# RP2040.net
KiCad netlist of a schematic drawn in Altium Designer
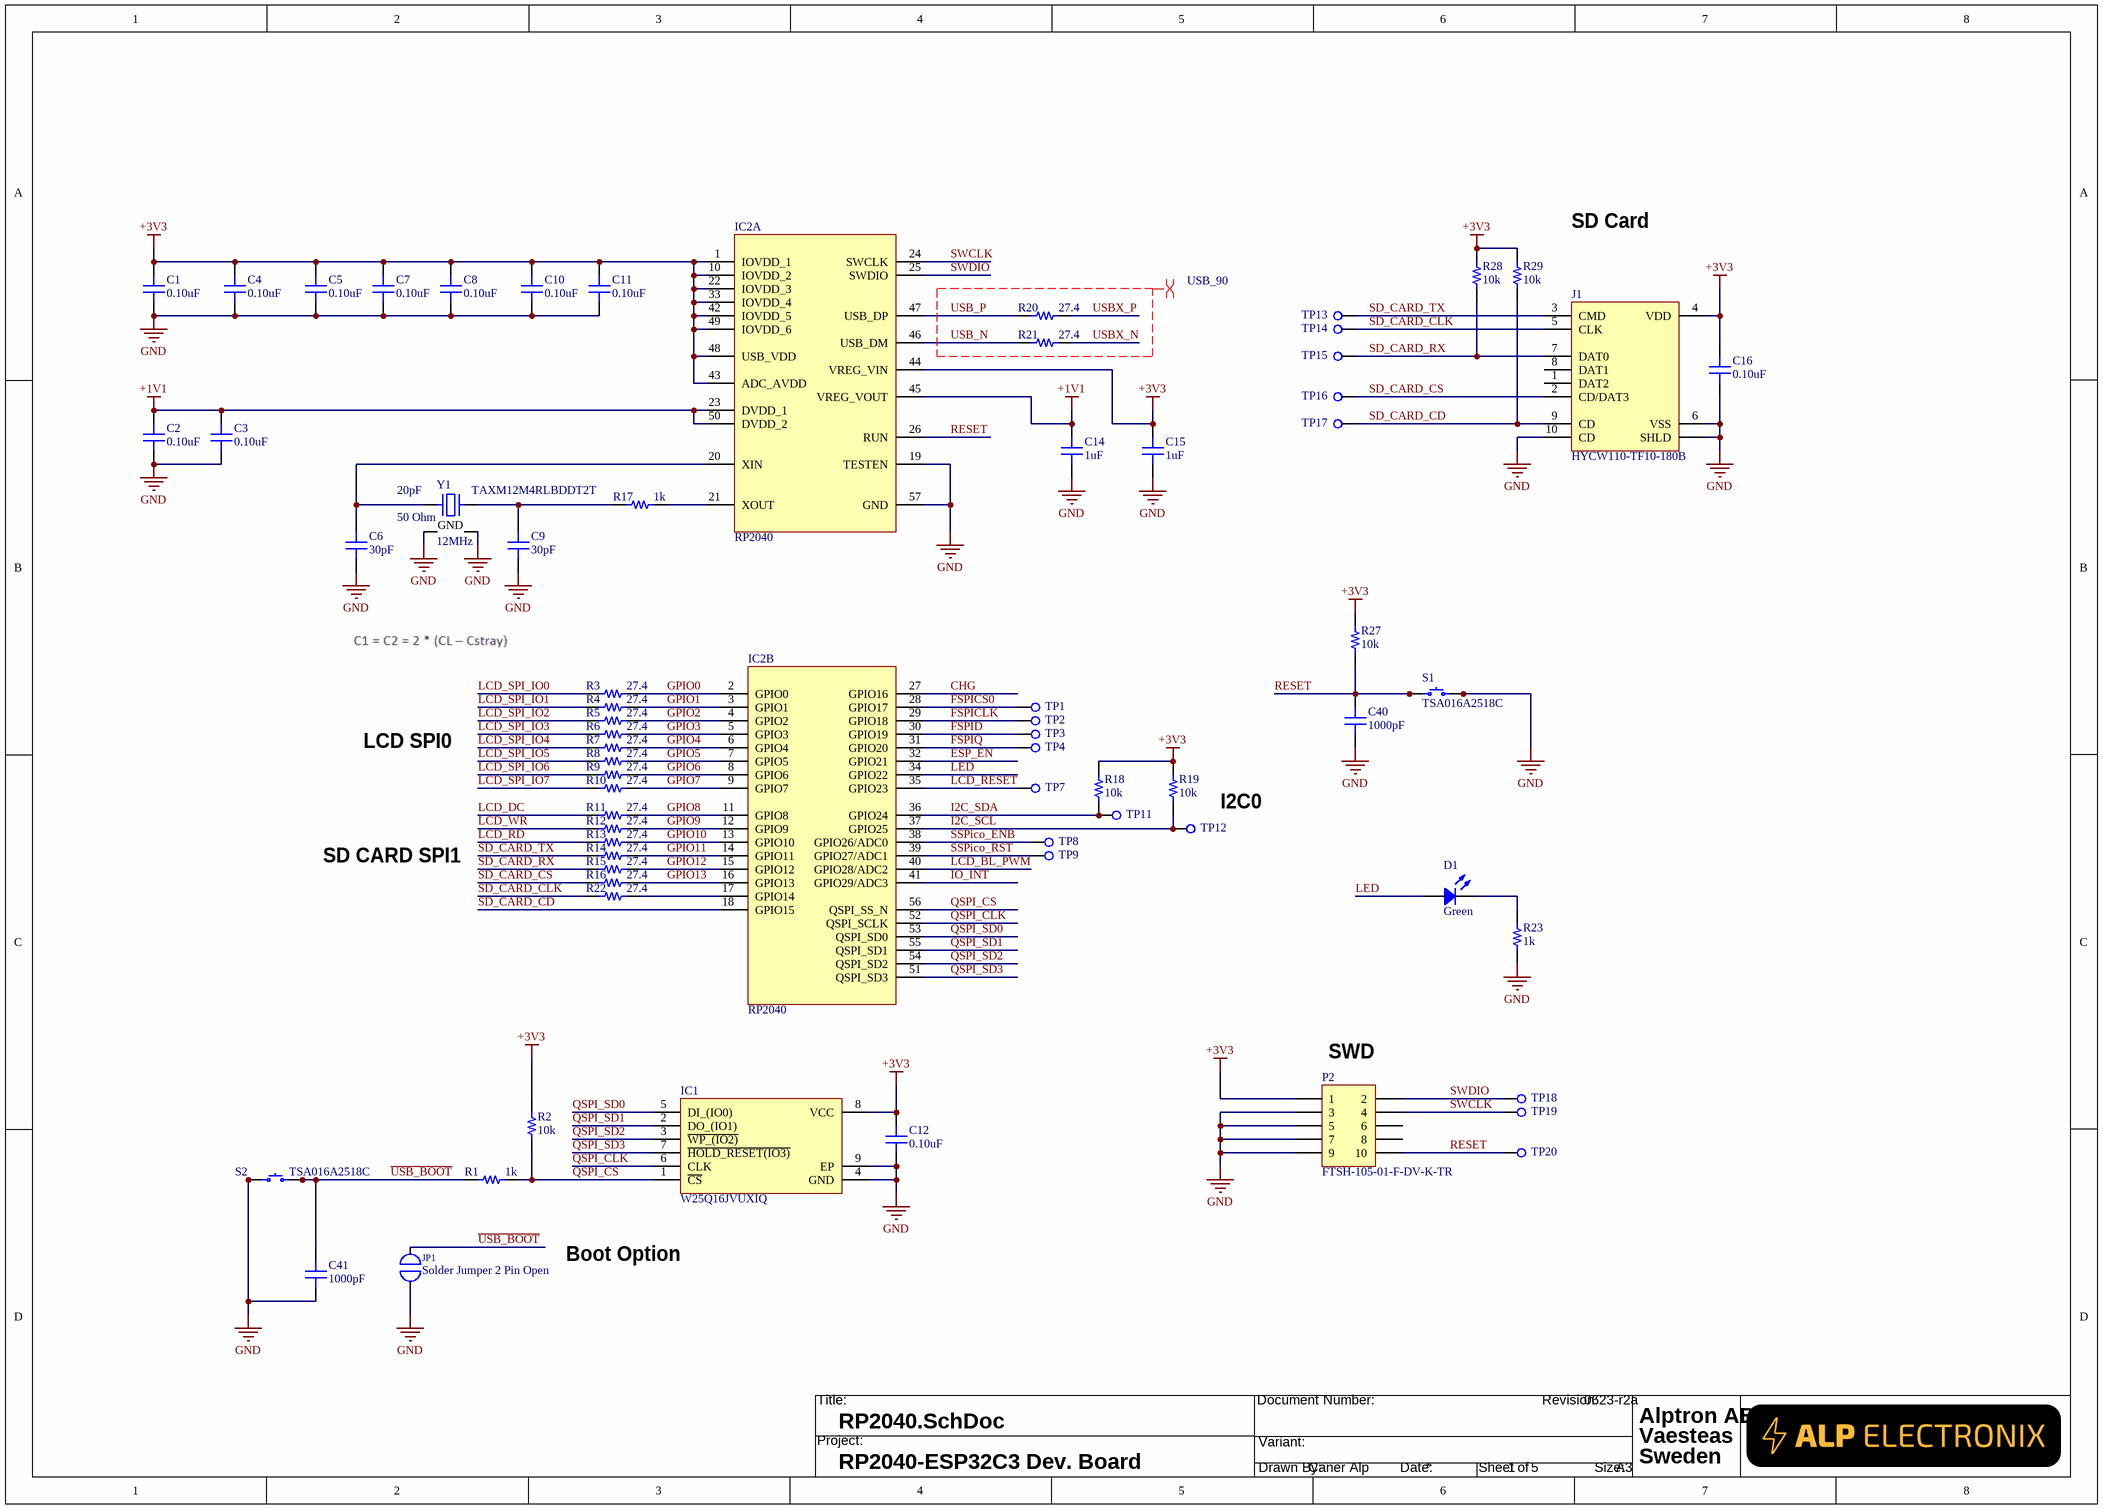
[diagram p0: RP2040.SchDoc]

(export (version "E")
  (design (tool "Eeschema 10.0.6"))
  (components
    (comp (ref "C1")
      (value "0.10uF")
      (footprint "CAP 0402/1005")
      (description "CAP CER 0.1UF 10V X5R 0402")
      (fields (field (name "PART NUMBER") "LMK105BJ104KV-F") (field (name "MANUFACTURER") "Taiyo Yuden"))
      (libsource (lib "Celestial Library Database") (part "Capacitor"))
    )
    (comp (ref "C2")
      (value "0.10uF")
      (footprint "CAP 0402/1005")
      (description "CAP CER 0.1UF 10V X5R 0402")
      (fields (field (name "PART NUMBER") "LMK105BJ104KV-F") (field (name "MANUFACTURER") "Taiyo Yuden"))
      (libsource (lib "Celestial Library Database") (part "Capacitor"))
    )
    (comp (ref "C3")
      (value "0.10uF")
      (footprint "CAP 0402/1005")
      (description "CAP CER 0.1UF 10V X5R 0402")
      (fields (field (name "PART NUMBER") "LMK105BJ104KV-F") (field (name "MANUFACTURER") "Taiyo Yuden"))
      (libsource (lib "Celestial Library Database") (part "Capacitor"))
    )
    (comp (ref "C4")
      (value "0.10uF")
      (footprint "CAP 0402/1005")
      (description "CAP CER 0.1UF 10V X5R 0402")
      (fields (field (name "PART NUMBER") "LMK105BJ104KV-F") (field (name "MANUFACTURER") "Taiyo Yuden"))
      (libsource (lib "Celestial Library Database") (part "Capacitor"))
    )
    (comp (ref "C5")
      (value "0.10uF")
      (footprint "CAP 0402/1005")
      (description "CAP CER 0.1UF 10V X5R 0402")
      (fields (field (name "PART NUMBER") "LMK105BJ104KV-F") (field (name "MANUFACTURER") "Taiyo Yuden"))
      (libsource (lib "Celestial Library Database") (part "Capacitor"))
    )
    (comp (ref "C6")
      (value "30pF")
      (footprint "CAP 0402/1005")
      (description "CAP CER 30PF 50V NP0 0402")
      (fields
        (field (name "PART NUMBER") "GRM1555C1H300JA01D")
        (field (name "MANUFACTURER") "Murata Electronics North America")
      )
      (libsource (lib "Celestial Library Database") (part "Capacitor"))
    )
    (comp (ref "C7")
      (value "0.10uF")
      (footprint "CAP 0402/1005")
      (description "CAP CER 0.1UF 10V X5R 0402")
      (fields (field (name "PART NUMBER") "LMK105BJ104KV-F") (field (name "MANUFACTURER") "Taiyo Yuden"))
      (libsource (lib "Celestial Library Database") (part "Capacitor"))
    )
    (comp (ref "C8")
      (value "0.10uF")
      (footprint "CAP 0402/1005")
      (description "CAP CER 0.1UF 10V X5R 0402")
      (fields (field (name "PART NUMBER") "LMK105BJ104KV-F") (field (name "MANUFACTURER") "Taiyo Yuden"))
      (libsource (lib "Celestial Library Database") (part "Capacitor"))
    )
    (comp (ref "C9")
      (value "30pF")
      (footprint "CAP 0402/1005")
      (description "CAP CER 30PF 50V NP0 0402")
      (fields
        (field (name "PART NUMBER") "GRM1555C1H300JA01D")
        (field (name "MANUFACTURER") "Murata Electronics North America")
      )
      (libsource (lib "Celestial Library Database") (part "Capacitor"))
    )
    (comp (ref "C10")
      (value "0.10uF")
      (footprint "CAP 0402/1005")
      (description "CAP CER 0.1UF 10V X5R 0402")
      (fields (field (name "PART NUMBER") "LMK105BJ104KV-F") (field (name "MANUFACTURER") "Taiyo Yuden"))
      (libsource (lib "Celestial Library Database") (part "Capacitor"))
    )
    (comp (ref "C11")
      (value "0.10uF")
      (footprint "CAP 0402/1005")
      (description "CAP CER 0.1UF 10V X5R 0402")
      (fields (field (name "PART NUMBER") "LMK105BJ104KV-F") (field (name "MANUFACTURER") "Taiyo Yuden"))
      (libsource (lib "Celestial Library Database") (part "Capacitor"))
    )
    (comp (ref "C12")
      (value "0.10uF")
      (footprint "CAP 0402/1005")
      (description "CAP CER 0.1UF 10V X5R 0402")
      (fields (field (name "PART NUMBER") "LMK105BJ104KV-F") (field (name "MANUFACTURER") "Taiyo Yuden"))
      (libsource (lib "Celestial Library Database") (part "Capacitor"))
    )
    (comp (ref "C14")
      (value "1uF")
      (footprint "CAP 0402/1005")
      (description "CAP CER 1UF 6.3V X7R 0402")
      (fields
        (field (name "PART NUMBER") "GRM155R70J105KA12D")
        (field (name "MANUFACTURER") "Murata Electronics North America")
      )
      (libsource (lib "Celestial Library Database") (part "Capacitor"))
    )
    (comp (ref "C15")
      (value "1uF")
      (footprint "CAP 0402/1005")
      (description "CAP CER 1UF 6.3V X7R 0402")
      (fields
        (field (name "PART NUMBER") "GRM155R70J105KA12D")
        (field (name "MANUFACTURER") "Murata Electronics North America")
      )
      (libsource (lib "Celestial Library Database") (part "Capacitor"))
    )
    (comp (ref "C16")
      (value "0.10uF")
      (footprint "CAP 0402/1005")
      (description "CAP CER 0.1UF 10V X5R 0402")
      (fields (field (name "PART NUMBER") "LMK105BJ104KV-F") (field (name "MANUFACTURER") "Taiyo Yuden"))
      (libsource (lib "Celestial Library Database") (part "Capacitor"))
    )
    (comp (ref "C40")
      (value "1000pF")
      (footprint "CAP 0402/1005")
      (description "CAP CER 1000PF 50V C0G 0402")
      (fields
        (field (name "PART NUMBER") "C1005C0G1H102J050BA")
        (field (name "MANUFACTURER") "TDK Corporation")
      )
      (libsource (lib "Celestial Library Database") (part "Capacitor"))
    )
    (comp (ref "C41")
      (value "1000pF")
      (footprint "CAP 0402/1005")
      (description "CAP CER 1000PF 50V C0G 0402")
      (fields
        (field (name "PART NUMBER") "C1005C0G1H102J050BA")
        (field (name "MANUFACTURER") "TDK Corporation")
      )
      (libsource (lib "Celestial Library Database") (part "Capacitor"))
    )
    (comp (ref "D1")
      (value "Green")
      (footprint "LED 0603/1608 GREEN")
      (description "LED GREEN DIFFUSED 0603 SMD")
      (fields
        (field (name "PART NUMBER") "HSMQ-C191")
        (field (name "MANUFACTURER") "Avago Technologies US Inc.")
      )
      (libsource (lib "Celestial Library Database") (part "LED"))
    )
    (comp (ref "IC1")
      (value "W25Q16JVUXIQ")
      (footprint "RP2040_ESP32-C3 Dev Board PCB Lib:SON50P300X200X60-9N")
      (description "Integrated Circuit")
      (libsource (lib "RP2040_ESP32-C3 Dev Board SCH Lib") (part "W25Q16JVUXIQ"))
    )
    (comp (ref "IC2")
      (value "RP2040")
      (footprint "RP2040_ESP32-C3 Dev Board PCB Lib:QFN40P700X700X90-57N-D")
      (description "Integrated Circuit")
      (libsource (lib "RP2040_ESP32-C3 Dev Board SCH Lib") (part "RP2040"))
    )
    (comp (ref "J1")
      (value "HYCW110-TF10-180B")
      (footprint "HYCW110-TF10-180B")
      (description "MICRO SD PUSH/PUSH SMALL 8C")
      (fields (field (name "MANUFACTURER") "SHOU HAN"))
      (libsource (lib "RP2040_ESP32-C3 Dev Board SCH Lib") (part "HYCW110-TF10-180B"))
    )
    (comp (ref "JP1")
      (value "Solder Jumper 2 Pin Open")
      (footprint "Jumper:SolderJumper-2_P1.3mm_Open_RoundedPad1.0x1.5mm")
      (libsource (lib "Jumper") (part "SolderJumper_2_Open"))
    )
    (comp (ref "P2")
      (value "FTSH-105-01-F-DV-K-TR")
      (footprint "3D FootPrint_Backup:FTSH-105-01-F-DV-K-TR")
      (description "Header, 5-Pin, Dual row")
      (fields (field (name "PUBLISHER") "Altium Limited"))
      (libsource (lib "Miscellaneous Connectors") (part "Header 5X2"))
    )
    (comp (ref "R1")
      (value "1k")
      (footprint "RES 0402/1005")
      (description "RES SMD 1K OHM 5% 1/10W 0402")
      (fields
        (field (name "PART NUMBER") "ERJ-2GEJ102X")
        (field (name "MANUFACTURER") "Panasonic Electronic Components")
      )
      (libsource (lib "Celestial Library Database") (part "Resistor"))
    )
    (comp (ref "R2")
      (value "10k")
      (footprint "RES 0402/1005")
      (description "RES SMD 10K OHM 5% 1/16W 0402")
      (fields (field (name "PART NUMBER") "RC0402JR-0710KL") (field (name "MANUFACTURER") "Yageo"))
      (libsource (lib "Celestial Library Database") (part "Resistor"))
    )
    (comp (ref "R3")
      (value "27.4")
      (footprint "RES 0402/1005")
      (description "RES SMD 27.4 OHM 1% 1/10W 0402")
      (fields
        (field (name "PART NUMBER") "ERJ-2RKF27R4X")
        (field (name "MANUFACTURER") "Panasonic Electronic Components")
      )
      (libsource (lib "Celestial Library Database") (part "Resistor"))
    )
    (comp (ref "R4")
      (value "27.4")
      (footprint "RES 0402/1005")
      (description "RES SMD 27.4 OHM 1% 1/10W 0402")
      (fields
        (field (name "PART NUMBER") "ERJ-2RKF27R4X")
        (field (name "MANUFACTURER") "Panasonic Electronic Components")
      )
      (libsource (lib "Celestial Library Database") (part "Resistor"))
    )
    (comp (ref "R5")
      (value "27.4")
      (footprint "RES 0402/1005")
      (description "RES SMD 27.4 OHM 1% 1/10W 0402")
      (fields
        (field (name "PART NUMBER") "ERJ-2RKF27R4X")
        (field (name "MANUFACTURER") "Panasonic Electronic Components")
      )
      (libsource (lib "Celestial Library Database") (part "Resistor"))
    )
    (comp (ref "R6")
      (value "27.4")
      (footprint "RES 0402/1005")
      (description "RES SMD 27.4 OHM 1% 1/10W 0402")
      (fields
        (field (name "PART NUMBER") "ERJ-2RKF27R4X")
        (field (name "MANUFACTURER") "Panasonic Electronic Components")
      )
      (libsource (lib "Celestial Library Database") (part "Resistor"))
    )
    (comp (ref "R7")
      (value "27.4")
      (footprint "RES 0402/1005")
      (description "RES SMD 27.4 OHM 1% 1/10W 0402")
      (fields
        (field (name "PART NUMBER") "ERJ-2RKF27R4X")
        (field (name "MANUFACTURER") "Panasonic Electronic Components")
      )
      (libsource (lib "Celestial Library Database") (part "Resistor"))
    )
    (comp (ref "R8")
      (value "27.4")
      (footprint "RES 0402/1005")
      (description "RES SMD 27.4 OHM 1% 1/10W 0402")
      (fields
        (field (name "PART NUMBER") "ERJ-2RKF27R4X")
        (field (name "MANUFACTURER") "Panasonic Electronic Components")
      )
      (libsource (lib "Celestial Library Database") (part "Resistor"))
    )
    (comp (ref "R9")
      (value "27.4")
      (footprint "RES 0402/1005")
      (description "RES SMD 27.4 OHM 1% 1/10W 0402")
      (fields
        (field (name "PART NUMBER") "ERJ-2RKF27R4X")
        (field (name "MANUFACTURER") "Panasonic Electronic Components")
      )
      (libsource (lib "Celestial Library Database") (part "Resistor"))
    )
    (comp (ref "R10")
      (value "27.4")
      (footprint "RES 0402/1005")
      (description "RES SMD 27.4 OHM 1% 1/10W 0402")
      (fields
        (field (name "PART NUMBER") "ERJ-2RKF27R4X")
        (field (name "MANUFACTURER") "Panasonic Electronic Components")
      )
      (libsource (lib "Celestial Library Database") (part "Resistor"))
    )
    (comp (ref "R11")
      (value "27.4")
      (footprint "RES 0402/1005")
      (description "RES SMD 27.4 OHM 1% 1/10W 0402")
      (fields
        (field (name "PART NUMBER") "ERJ-2RKF27R4X")
        (field (name "MANUFACTURER") "Panasonic Electronic Components")
      )
      (libsource (lib "Celestial Library Database") (part "Resistor"))
    )
    (comp (ref "R12")
      (value "27.4")
      (footprint "RES 0402/1005")
      (description "RES SMD 27.4 OHM 1% 1/10W 0402")
      (fields
        (field (name "PART NUMBER") "ERJ-2RKF27R4X")
        (field (name "MANUFACTURER") "Panasonic Electronic Components")
      )
      (libsource (lib "Celestial Library Database") (part "Resistor"))
    )
    (comp (ref "R13")
      (value "27.4")
      (footprint "RES 0402/1005")
      (description "RES SMD 27.4 OHM 1% 1/10W 0402")
      (fields
        (field (name "PART NUMBER") "ERJ-2RKF27R4X")
        (field (name "MANUFACTURER") "Panasonic Electronic Components")
      )
      (libsource (lib "Celestial Library Database") (part "Resistor"))
    )
    (comp (ref "R14")
      (value "27.4")
      (footprint "RES 0402/1005")
      (description "RES SMD 27.4 OHM 1% 1/10W 0402")
      (fields
        (field (name "PART NUMBER") "ERJ-2RKF27R4X")
        (field (name "MANUFACTURER") "Panasonic Electronic Components")
      )
      (libsource (lib "Celestial Library Database") (part "Resistor"))
    )
    (comp (ref "R15")
      (value "27.4")
      (footprint "RES 0402/1005")
      (description "RES SMD 27.4 OHM 1% 1/10W 0402")
      (fields
        (field (name "PART NUMBER") "ERJ-2RKF27R4X")
        (field (name "MANUFACTURER") "Panasonic Electronic Components")
      )
      (libsource (lib "Celestial Library Database") (part "Resistor"))
    )
    (comp (ref "R16")
      (value "27.4")
      (footprint "RES 0402/1005")
      (description "RES SMD 27.4 OHM 1% 1/10W 0402")
      (fields
        (field (name "PART NUMBER") "ERJ-2RKF27R4X")
        (field (name "MANUFACTURER") "Panasonic Electronic Components")
      )
      (libsource (lib "Celestial Library Database") (part "Resistor"))
    )
    (comp (ref "R17")
      (value "1k")
      (footprint "RES 0402/1005")
      (description "RES SMD 1K OHM 5% 1/10W 0402")
      (fields
        (field (name "PART NUMBER") "ERJ-2GEJ102X")
        (field (name "MANUFACTURER") "Panasonic Electronic Components")
      )
      (libsource (lib "Celestial Library Database") (part "Resistor"))
    )
    (comp (ref "R18")
      (value "10k")
      (footprint "RES 0402/1005")
      (description "RES SMD 10K OHM 5% 1/16W 0402")
      (fields (field (name "PART NUMBER") "RC0402JR-0710KL") (field (name "MANUFACTURER") "Yageo"))
      (libsource (lib "Celestial Library Database") (part "Resistor"))
    )
    (comp (ref "R19")
      (value "10k")
      (footprint "RES 0402/1005")
      (description "RES SMD 10K OHM 5% 1/16W 0402")
      (fields (field (name "PART NUMBER") "RC0402JR-0710KL") (field (name "MANUFACTURER") "Yageo"))
      (libsource (lib "Celestial Library Database") (part "Resistor"))
    )
    (comp (ref "R20")
      (value "27.4")
      (footprint "RES 0402/1005")
      (description "RES SMD 27.4 OHM 1% 1/10W 0402")
      (fields
        (field (name "PART NUMBER") "ERJ-2RKF27R4X")
        (field (name "MANUFACTURER") "Panasonic Electronic Components")
      )
      (libsource (lib "Celestial Library Database") (part "Resistor"))
    )
    (comp (ref "R21")
      (value "27.4")
      (footprint "RES 0402/1005")
      (description "RES SMD 27.4 OHM 1% 1/10W 0402")
      (fields
        (field (name "PART NUMBER") "ERJ-2RKF27R4X")
        (field (name "MANUFACTURER") "Panasonic Electronic Components")
      )
      (libsource (lib "Celestial Library Database") (part "Resistor"))
    )
    (comp (ref "R22")
      (value "27.4")
      (footprint "RES 0402/1005")
      (description "RES SMD 27.4 OHM 1% 1/10W 0402")
      (fields
        (field (name "PART NUMBER") "ERJ-2RKF27R4X")
        (field (name "MANUFACTURER") "Panasonic Electronic Components")
      )
      (libsource (lib "Celestial Library Database") (part "Resistor"))
    )
    (comp (ref "R23")
      (value "1k")
      (footprint "RES 0402/1005")
      (description "RES SMD 1K OHM 5% 1/10W 0402")
      (fields
        (field (name "PART NUMBER") "ERJ-2GEJ102X")
        (field (name "MANUFACTURER") "Panasonic Electronic Components")
      )
      (libsource (lib "Celestial Library Database") (part "Resistor"))
    )
    (comp (ref "R27")
      (value "10k")
      (footprint "RES 0402/1005")
      (description "RES SMD 10K OHM 5% 1/16W 0402")
      (fields (field (name "PART NUMBER") "RC0402JR-0710KL") (field (name "MANUFACTURER") "Yageo"))
      (libsource (lib "Celestial Library Database") (part "Resistor"))
    )
    (comp (ref "R28")
      (value "10k")
      (footprint "RES 0402/1005")
      (description "RES SMD 10K OHM 5% 1/16W 0402")
      (fields (field (name "PART NUMBER") "RC0402JR-0710KL") (field (name "MANUFACTURER") "Yageo"))
      (libsource (lib "Celestial Library Database") (part "Resistor"))
    )
    (comp (ref "R29")
      (value "10k")
      (footprint "RES 0402/1005")
      (description "RES SMD 10K OHM 5% 1/16W 0402")
      (fields (field (name "PART NUMBER") "RC0402JR-0710KL") (field (name "MANUFACTURER") "Yageo"))
      (libsource (lib "Celestial Library Database") (part "Resistor"))
    )
    (comp (ref "S1")
      (value "TSA016A2518C")
      (footprint "RP2040_ESP32-C3 Dev Board PCB Lib:TSA016A2518C")
      (description "SWITCH TACTILE SPST-NO 0.05A 16V")
      (fields (field (name "MANUFACTURER") "C&K"))
      (libsource (lib "Celestial Altium Library - altium_library") (part "SPST-NO 4 PIN"))
    )
    (comp (ref "S2")
      (value "TSA016A2518C")
      (footprint "RP2040_ESP32-C3 Dev Board PCB Lib:TSA016A2518C")
      (description "SWITCH TACTILE SPST-NO 0.05A 16V")
      (fields (field (name "MANUFACTURER") "C&K"))
      (libsource (lib "Celestial Altium Library - altium_library") (part "SPST-NO 4 PIN"))
    )
    (comp (ref "TP1")
      (value "RCT-0C")
      (footprint "RP2040_ESP32-C3 Dev Board PCB Lib:TestPoint 1mm")
      (description "0805 PROBE PAD")
      (fields (field (name "MANUFACTURER") "TE Connectivity AMP Connectors"))
      (libsource (lib "Celestial Library Database") (part "Test Point"))
    )
    (comp (ref "TP2")
      (value "RCT-0C")
      (footprint "RP2040_ESP32-C3 Dev Board PCB Lib:TestPoint 1mm")
      (description "0805 PROBE PAD")
      (fields (field (name "MANUFACTURER") "TE Connectivity AMP Connectors"))
      (libsource (lib "Celestial Library Database") (part "Test Point"))
    )
    (comp (ref "TP3")
      (value "RCT-0C")
      (footprint "RP2040_ESP32-C3 Dev Board PCB Lib:TestPoint 1mm")
      (description "0805 PROBE PAD")
      (fields (field (name "MANUFACTURER") "TE Connectivity AMP Connectors"))
      (libsource (lib "Celestial Library Database") (part "Test Point"))
    )
    (comp (ref "TP4")
      (value "RCT-0C")
      (footprint "RP2040_ESP32-C3 Dev Board PCB Lib:TestPoint 1mm")
      (description "0805 PROBE PAD")
      (fields (field (name "MANUFACTURER") "TE Connectivity AMP Connectors"))
      (libsource (lib "Celestial Library Database") (part "Test Point"))
    )
    (comp (ref "TP7")
      (value "RCT-0C")
      (footprint "RP2040_ESP32-C3 Dev Board PCB Lib:TestPoint 1mm")
      (description "0805 PROBE PAD")
      (fields (field (name "MANUFACTURER") "TE Connectivity AMP Connectors"))
      (libsource (lib "Celestial Library Database") (part "Test Point"))
    )
    (comp (ref "TP8")
      (value "RCT-0C")
      (footprint "RP2040_ESP32-C3 Dev Board PCB Lib:TestPoint 1mm")
      (description "0805 PROBE PAD")
      (fields (field (name "MANUFACTURER") "TE Connectivity AMP Connectors"))
      (libsource (lib "Celestial Library Database") (part "Test Point"))
    )
    (comp (ref "TP9")
      (value "RCT-0C")
      (footprint "RP2040_ESP32-C3 Dev Board PCB Lib:TestPoint 1mm")
      (description "0805 PROBE PAD")
      (fields (field (name "MANUFACTURER") "TE Connectivity AMP Connectors"))
      (libsource (lib "Celestial Library Database") (part "Test Point"))
    )
    (comp (ref "TP11")
      (value "RCT-0C")
      (footprint "RP2040_ESP32-C3 Dev Board PCB Lib:TestPoint 1mm")
      (description "0805 PROBE PAD")
      (fields (field (name "MANUFACTURER") "TE Connectivity AMP Connectors"))
      (libsource (lib "Celestial Library Database") (part "Test Point"))
    )
    (comp (ref "TP12")
      (value "RCT-0C")
      (footprint "RP2040_ESP32-C3 Dev Board PCB Lib:TestPoint 1mm")
      (description "0805 PROBE PAD")
      (fields (field (name "MANUFACTURER") "TE Connectivity AMP Connectors"))
      (libsource (lib "Celestial Library Database") (part "Test Point"))
    )
    (comp (ref "TP13")
      (value "RCT-0C")
      (footprint "RP2040_ESP32-C3 Dev Board PCB Lib:TestPoint 1mm")
      (description "0805 PROBE PAD")
      (fields (field (name "MANUFACTURER") "TE Connectivity AMP Connectors"))
      (libsource (lib "Celestial Library Database") (part "Test Point"))
    )
    (comp (ref "TP14")
      (value "RCT-0C")
      (footprint "RP2040_ESP32-C3 Dev Board PCB Lib:TestPoint 1mm")
      (description "0805 PROBE PAD")
      (fields (field (name "MANUFACTURER") "TE Connectivity AMP Connectors"))
      (libsource (lib "Celestial Library Database") (part "Test Point"))
    )
    (comp (ref "TP15")
      (value "RCT-0C")
      (footprint "RP2040_ESP32-C3 Dev Board PCB Lib:TestPoint 1mm")
      (description "0805 PROBE PAD")
      (fields (field (name "MANUFACTURER") "TE Connectivity AMP Connectors"))
      (libsource (lib "Celestial Library Database") (part "Test Point"))
    )
    (comp (ref "TP16")
      (value "RCT-0C")
      (footprint "RP2040_ESP32-C3 Dev Board PCB Lib:TestPoint 1mm")
      (description "0805 PROBE PAD")
      (fields (field (name "MANUFACTURER") "TE Connectivity AMP Connectors"))
      (libsource (lib "Celestial Library Database") (part "Test Point"))
    )
    (comp (ref "TP17")
      (value "RCT-0C")
      (footprint "RP2040_ESP32-C3 Dev Board PCB Lib:TestPoint 1mm")
      (description "0805 PROBE PAD")
      (fields (field (name "MANUFACTURER") "TE Connectivity AMP Connectors"))
      (libsource (lib "Celestial Library Database") (part "Test Point"))
    )
    (comp (ref "TP18")
      (value "RCT-0C")
      (footprint "RP2040_ESP32-C3 Dev Board PCB Lib:TestPoint 1mm")
      (description "0805 PROBE PAD")
      (fields (field (name "MANUFACTURER") "TE Connectivity AMP Connectors"))
      (libsource (lib "Celestial Library Database") (part "Test Point"))
    )
    (comp (ref "TP19")
      (value "RCT-0C")
      (footprint "RP2040_ESP32-C3 Dev Board PCB Lib:TestPoint 1mm")
      (description "0805 PROBE PAD")
      (fields (field (name "MANUFACTURER") "TE Connectivity AMP Connectors"))
      (libsource (lib "Celestial Library Database") (part "Test Point"))
    )
    (comp (ref "TP20")
      (value "RCT-0C")
      (footprint "RP2040_ESP32-C3 Dev Board PCB Lib:TestPoint 1mm")
      (description "0805 PROBE PAD")
      (fields (field (name "MANUFACTURER") "TE Connectivity AMP Connectors"))
      (libsource (lib "Celestial Library Database") (part "Test Point"))
    )
    (comp (ref "Y1")
      (value "12MHz")
      (footprint "NDK NX3225SA")
      (description "CRYSTAL 12.0000MHZ 8PF SMD")
      (fields
        (field (name "PART NUMBER") "TAXM12M4RLBDDT2T")
        (field (name "MANUFACTURER") "NDK")
        (field (name "LOAD CAPACITANCE") "20pF")
        (field (name "ESR") "50 Ohm")
      )
      (libsource (lib "Celestial Library Database") (part "NDK Crystal NX3225SA"))
    )
  )
  (nets
    (net (code "1") (name "+1V1") (class "Default")
      (node (ref "C14") (pin "2") (pinfunction "2_2") (pintype "passive"))
      (node (ref "C2") (pin "2") (pinfunction "2_2") (pintype "passive"))
      (node (ref "C3") (pin "2") (pinfunction "2_2") (pintype "passive"))
      (node (ref "IC2") (pin "23") (pinfunction "DVDD_1_23") (pintype "passive"))
      (node (ref "IC2") (pin "45") (pinfunction "VREG_VOUT_45") (pintype "passive"))
      (node (ref "IC2") (pin "50") (pinfunction "DVDD_2_50") (pintype "passive"))
    )
    (net (code "2") (name "+3V3") (class "Default")
      (node (ref "C1") (pin "2") (pinfunction "2_2") (pintype "passive"))
      (node (ref "C10") (pin "2") (pinfunction "2_2") (pintype "passive"))
      (node (ref "C11") (pin "2") (pinfunction "2_2") (pintype "passive"))
      (node (ref "C12") (pin "2") (pinfunction "2_2") (pintype "passive"))
      (node (ref "C15") (pin "2") (pinfunction "2_2") (pintype "passive"))
      (node (ref "C16") (pin "2") (pinfunction "2_2") (pintype "passive"))
      (node (ref "C4") (pin "2") (pinfunction "2_2") (pintype "passive"))
      (node (ref "C5") (pin "2") (pinfunction "2_2") (pintype "passive"))
      (node (ref "C7") (pin "2") (pinfunction "2_2") (pintype "passive"))
      (node (ref "C8") (pin "2") (pinfunction "2_2") (pintype "passive"))
      (node (ref "IC1") (pin "8") (pinfunction "VCC_8") (pintype "passive"))
      (node (ref "IC2") (pin "1") (pinfunction "IOVDD_1_1") (pintype "passive"))
      (node (ref "IC2") (pin "10") (pinfunction "IOVDD_2_10") (pintype "passive"))
      (node (ref "IC2") (pin "22") (pinfunction "IOVDD_3_22") (pintype "passive"))
      (node (ref "IC2") (pin "33") (pinfunction "IOVDD_4_33") (pintype "passive"))
      (node (ref "IC2") (pin "42") (pinfunction "IOVDD_5_42") (pintype "passive"))
      (node (ref "IC2") (pin "43") (pinfunction "ADC_AVDD_43") (pintype "passive"))
      (node (ref "IC2") (pin "44") (pinfunction "VREG_VIN_44") (pintype "passive"))
      (node (ref "IC2") (pin "48") (pinfunction "USB_VDD_48") (pintype "passive"))
      (node (ref "IC2") (pin "49") (pinfunction "IOVDD_6_49") (pintype "passive"))
      (node (ref "J1") (pin "4") (pinfunction "VDD_4") (pintype "passive"))
      (node (ref "P2") (pin "1") (pinfunction "1_1") (pintype "passive"))
      (node (ref "R18") (pin "2") (pinfunction "2_2") (pintype "passive"))
      (node (ref "R19") (pin "2") (pinfunction "2_2") (pintype "passive"))
      (node (ref "R2") (pin "2") (pinfunction "2_2") (pintype "passive"))
      (node (ref "R27") (pin "2") (pinfunction "2_2") (pintype "passive"))
      (node (ref "R28") (pin "2") (pinfunction "2_2") (pintype "passive"))
      (node (ref "R29") (pin "2") (pinfunction "2_2") (pintype "passive"))
    )
    (net (code "3") (name "/CHG") (class "Default")
      (node (ref "IC2") (pin "27") (pinfunction "GPIO16_27") (pintype "passive"))
    )
    (net (code "4") (name "/ESP_EN") (class "Default")
      (node (ref "IC2") (pin "32") (pinfunction "GPIO21_32") (pintype "passive"))
    )
    (net (code "5") (name "/FSPICLK") (class "Default")
      (node (ref "IC2") (pin "29") (pinfunction "GPIO18_29") (pintype "passive"))
      (node (ref "TP2") (pin "1") (pinfunction "TP_1") (pintype "passive"))
    )
    (net (code "6") (name "/FSPICS0") (class "Default")
      (node (ref "IC2") (pin "28") (pinfunction "GPIO17_28") (pintype "passive"))
      (node (ref "TP1") (pin "1") (pinfunction "TP_1") (pintype "passive"))
    )
    (net (code "7") (name "/FSPID") (class "Default")
      (node (ref "IC2") (pin "30") (pinfunction "GPIO19_30") (pintype "passive"))
      (node (ref "TP3") (pin "1") (pinfunction "TP_1") (pintype "passive"))
    )
    (net (code "8") (name "/FSPIQ") (class "Default")
      (node (ref "IC2") (pin "31") (pinfunction "GPIO20_31") (pintype "passive"))
      (node (ref "TP4") (pin "1") (pinfunction "TP_1") (pintype "passive"))
    )
    (net (code "9") (name "/GPIO0") (class "Default")
      (node (ref "IC2") (pin "2") (pinfunction "GPIO0_2") (pintype "passive"))
      (node (ref "R3") (pin "2") (pinfunction "2_2") (pintype "passive"))
    )
    (net (code "10") (name "/GPIO1") (class "Default")
      (node (ref "IC2") (pin "3") (pinfunction "GPIO1_3") (pintype "passive"))
      (node (ref "R4") (pin "2") (pinfunction "2_2") (pintype "passive"))
    )
    (net (code "11") (name "/GPIO2") (class "Default")
      (node (ref "IC2") (pin "4") (pinfunction "GPIO2_4") (pintype "passive"))
      (node (ref "R5") (pin "2") (pinfunction "2_2") (pintype "passive"))
    )
    (net (code "12") (name "/GPIO3") (class "Default")
      (node (ref "IC2") (pin "5") (pinfunction "GPIO3_5") (pintype "passive"))
      (node (ref "R6") (pin "2") (pinfunction "2_2") (pintype "passive"))
    )
    (net (code "13") (name "/GPIO4") (class "Default")
      (node (ref "IC2") (pin "6") (pinfunction "GPIO4_6") (pintype "passive"))
      (node (ref "R7") (pin "2") (pinfunction "2_2") (pintype "passive"))
    )
    (net (code "14") (name "/GPIO5") (class "Default")
      (node (ref "IC2") (pin "7") (pinfunction "GPIO5_7") (pintype "passive"))
      (node (ref "R8") (pin "2") (pinfunction "2_2") (pintype "passive"))
    )
    (net (code "15") (name "/GPIO6") (class "Default")
      (node (ref "IC2") (pin "8") (pinfunction "GPIO6_8") (pintype "passive"))
      (node (ref "R9") (pin "2") (pinfunction "2_2") (pintype "passive"))
    )
    (net (code "16") (name "/GPIO7") (class "Default")
      (node (ref "IC2") (pin "9") (pinfunction "GPIO7_9") (pintype "passive"))
      (node (ref "R10") (pin "2") (pinfunction "2_2") (pintype "passive"))
    )
    (net (code "17") (name "/GPIO8") (class "Default")
      (node (ref "IC2") (pin "11") (pinfunction "GPIO8_11") (pintype "passive"))
      (node (ref "R11") (pin "2") (pinfunction "2_2") (pintype "passive"))
    )
    (net (code "18") (name "/GPIO9") (class "Default")
      (node (ref "IC2") (pin "12") (pinfunction "GPIO9_12") (pintype "passive"))
      (node (ref "R12") (pin "2") (pinfunction "2_2") (pintype "passive"))
    )
    (net (code "19") (name "/GPIO10") (class "Default")
      (node (ref "IC2") (pin "13") (pinfunction "GPIO10_13") (pintype "passive"))
      (node (ref "R13") (pin "2") (pinfunction "2_2") (pintype "passive"))
    )
    (net (code "20") (name "/GPIO11") (class "Default")
      (node (ref "IC2") (pin "14") (pinfunction "GPIO11_14") (pintype "passive"))
      (node (ref "R14") (pin "2") (pinfunction "2_2") (pintype "passive"))
    )
    (net (code "21") (name "/GPIO12") (class "Default")
      (node (ref "IC2") (pin "15") (pinfunction "GPIO12_15") (pintype "passive"))
      (node (ref "R15") (pin "2") (pinfunction "2_2") (pintype "passive"))
    )
    (net (code "22") (name "/GPIO13") (class "Default")
      (node (ref "IC2") (pin "16") (pinfunction "GPIO13_16") (pintype "passive"))
      (node (ref "R16") (pin "2") (pinfunction "2_2") (pintype "passive"))
    )
    (net (code "23") (name "/I2C_SCL") (class "Default")
      (node (ref "IC2") (pin "37") (pinfunction "GPIO25_37") (pintype "passive"))
      (node (ref "R19") (pin "1") (pinfunction "1_1") (pintype "passive"))
      (node (ref "TP12") (pin "1") (pinfunction "TP_1") (pintype "passive"))
    )
    (net (code "24") (name "/I2C_SDA") (class "Default")
      (node (ref "IC2") (pin "36") (pinfunction "GPIO24_36") (pintype "passive"))
      (node (ref "R18") (pin "1") (pinfunction "1_1") (pintype "passive"))
      (node (ref "TP11") (pin "1") (pinfunction "TP_1") (pintype "passive"))
    )
    (net (code "25") (name "/IO_INT") (class "Default")
      (node (ref "IC2") (pin "41") (pinfunction "GPIO29/ADC3_41") (pintype "passive"))
    )
    (net (code "26") (name "/LCD_BL_PWM") (class "Default")
      (node (ref "IC2") (pin "40") (pinfunction "GPIO28/ADC2_40") (pintype "passive"))
    )
    (net (code "27") (name "/LCD_DC") (class "Default")
      (node (ref "R11") (pin "1") (pinfunction "1_1") (pintype "passive"))
    )
    (net (code "28") (name "/LCD_RD") (class "Default")
      (node (ref "R13") (pin "1") (pinfunction "1_1") (pintype "passive"))
    )
    (net (code "29") (name "/LCD_RESET") (class "Default")
      (node (ref "IC2") (pin "35") (pinfunction "GPIO23_35") (pintype "passive"))
      (node (ref "TP7") (pin "1") (pinfunction "TP_1") (pintype "passive"))
    )
    (net (code "30") (name "/LCD_SPI_IO0") (class "Default")
      (node (ref "R3") (pin "1") (pinfunction "1_1") (pintype "passive"))
    )
    (net (code "31") (name "/LCD_SPI_IO1") (class "Default")
      (node (ref "R4") (pin "1") (pinfunction "1_1") (pintype "passive"))
    )
    (net (code "32") (name "/LCD_SPI_IO2") (class "Default")
      (node (ref "R5") (pin "1") (pinfunction "1_1") (pintype "passive"))
    )
    (net (code "33") (name "/LCD_SPI_IO3") (class "Default")
      (node (ref "R6") (pin "1") (pinfunction "1_1") (pintype "passive"))
    )
    (net (code "34") (name "/LCD_SPI_IO4") (class "Default")
      (node (ref "R7") (pin "1") (pinfunction "1_1") (pintype "passive"))
    )
    (net (code "35") (name "/LCD_SPI_IO5") (class "Default")
      (node (ref "R8") (pin "1") (pinfunction "1_1") (pintype "passive"))
    )
    (net (code "36") (name "/LCD_SPI_IO6") (class "Default")
      (node (ref "R9") (pin "1") (pinfunction "1_1") (pintype "passive"))
    )
    (net (code "37") (name "/LCD_SPI_IO7") (class "Default")
      (node (ref "R10") (pin "1") (pinfunction "1_1") (pintype "passive"))
    )
    (net (code "38") (name "/LCD_WR") (class "Default")
      (node (ref "R12") (pin "1") (pinfunction "1_1") (pintype "passive"))
    )
    (net (code "39") (name "/LED") (class "Default")
      (node (ref "D1") (pin "1") (pinfunction "1_1") (pintype "passive"))
      (node (ref "IC2") (pin "34") (pinfunction "GPIO22_34") (pintype "passive"))
    )
    (net (code "40") (name "/QSPI_CLK") (class "Default")
      (node (ref "IC1") (pin "6") (pinfunction "CLK_6") (pintype "passive"))
      (node (ref "IC2") (pin "52") (pinfunction "QSPI_SCLK_52") (pintype "passive"))
    )
    (net (code "41") (name "/QSPI_CS") (class "Default")
      (node (ref "IC1") (pin "1") (pinfunction "~{CS}_1") (pintype "passive"))
      (node (ref "IC2") (pin "56") (pinfunction "QSPI_SS_N_56") (pintype "passive"))
      (node (ref "R1") (pin "2") (pinfunction "2_2") (pintype "passive"))
      (node (ref "R2") (pin "1") (pinfunction "1_1") (pintype "passive"))
    )
    (net (code "42") (name "/QSPI_SD0") (class "Default")
      (node (ref "IC1") (pin "5") (pinfunction "DI_(IO0)_5") (pintype "passive"))
      (node (ref "IC2") (pin "53") (pinfunction "QSPI_SD0_53") (pintype "passive"))
    )
    (net (code "43") (name "/QSPI_SD1") (class "Default")
      (node (ref "IC1") (pin "2") (pinfunction "DO_(IO1)_2") (pintype "passive"))
      (node (ref "IC2") (pin "55") (pinfunction "QSPI_SD1_55") (pintype "passive"))
    )
    (net (code "44") (name "/QSPI_SD2") (class "Default")
      (node (ref "IC1") (pin "3") (pinfunction "~{WP_(IO2)}_3") (pintype "passive"))
      (node (ref "IC2") (pin "54") (pinfunction "QSPI_SD2_54") (pintype "passive"))
    )
    (net (code "45") (name "/QSPI_SD3") (class "Default")
      (node (ref "IC1") (pin "7") (pinfunction "~{HOLD_RESET(IO3)}_7") (pintype "passive"))
      (node (ref "IC2") (pin "51") (pinfunction "QSPI_SD3_51") (pintype "passive"))
    )
    (net (code "46") (name "/RESET") (class "Default")
      (node (ref "C40") (pin "2") (pinfunction "2_2") (pintype "passive"))
      (node (ref "IC2") (pin "26") (pinfunction "RUN_26") (pintype "passive"))
      (node (ref "P2") (pin "10") (pinfunction "10_10") (pintype "passive"))
      (node (ref "R27") (pin "1") (pinfunction "1_1") (pintype "passive"))
      (node (ref "S1") (pin "1") (pinfunction "1_1") (pintype "passive"))
      (node (ref "S1") (pin "2") (pinfunction "2_2") (pintype "passive"))
      (node (ref "TP20") (pin "1") (pinfunction "TP_1") (pintype "passive"))
    )
    (net (code "47") (name "/SD_CARD_CD") (class "Default")
      (node (ref "IC2") (pin "18") (pinfunction "GPIO15_18") (pintype "passive"))
      (node (ref "J1") (pin "9") (pinfunction "CD_9") (pintype "passive"))
      (node (ref "R29") (pin "1") (pinfunction "1_1") (pintype "passive"))
      (node (ref "TP17") (pin "1") (pinfunction "TP_1") (pintype "passive"))
    )
    (net (code "48") (name "/SD_CARD_CLK") (class "Default")
      (node (ref "J1") (pin "5") (pinfunction "CLK_5") (pintype "passive"))
      (node (ref "R22") (pin "1") (pinfunction "1_1") (pintype "passive"))
      (node (ref "TP14") (pin "1") (pinfunction "TP_1") (pintype "passive"))
    )
    (net (code "49") (name "/SD_CARD_CS") (class "Default")
      (node (ref "J1") (pin "2") (pinfunction "CD/DAT3_2") (pintype "passive"))
      (node (ref "R16") (pin "1") (pinfunction "1_1") (pintype "passive"))
      (node (ref "TP16") (pin "1") (pinfunction "TP_1") (pintype "passive"))
    )
    (net (code "50") (name "/SD_CARD_RX") (class "Default")
      (node (ref "J1") (pin "7") (pinfunction "DAT0_7") (pintype "passive"))
      (node (ref "R15") (pin "1") (pinfunction "1_1") (pintype "passive"))
      (node (ref "R28") (pin "1") (pinfunction "1_1") (pintype "passive"))
      (node (ref "TP15") (pin "1") (pinfunction "TP_1") (pintype "passive"))
    )
    (net (code "51") (name "/SD_CARD_TX") (class "Default")
      (node (ref "J1") (pin "3") (pinfunction "CMD_3") (pintype "passive"))
      (node (ref "R14") (pin "1") (pinfunction "1_1") (pintype "passive"))
      (node (ref "TP13") (pin "1") (pinfunction "TP_1") (pintype "passive"))
    )
    (net (code "52") (name "/SSPico_ENB") (class "Default")
      (node (ref "IC2") (pin "38") (pinfunction "GPIO26/ADC0_38") (pintype "passive"))
      (node (ref "TP8") (pin "1") (pinfunction "TP_1") (pintype "passive"))
    )
    (net (code "53") (name "/SSPico_RST") (class "Default")
      (node (ref "IC2") (pin "39") (pinfunction "GPIO27/ADC1_39") (pintype "passive"))
      (node (ref "TP9") (pin "1") (pinfunction "TP_1") (pintype "passive"))
    )
    (net (code "54") (name "/SWCLK") (class "Default")
      (node (ref "IC2") (pin "24") (pinfunction "SWCLK_24") (pintype "passive"))
      (node (ref "P2") (pin "4") (pinfunction "4_4") (pintype "passive"))
      (node (ref "TP19") (pin "1") (pinfunction "TP_1") (pintype "passive"))
    )
    (net (code "55") (name "/SWDIO") (class "Default")
      (node (ref "IC2") (pin "25") (pinfunction "SWDIO_25") (pintype "passive"))
      (node (ref "P2") (pin "2") (pinfunction "2_2") (pintype "passive"))
      (node (ref "TP18") (pin "1") (pinfunction "TP_1") (pintype "passive"))
    )
    (net (code "56") (name "/USBX_N") (class "Default")
      (node (ref "R21") (pin "2") (pinfunction "2_2") (pintype "passive"))
    )
    (net (code "57") (name "/USBX_P") (class "Default")
      (node (ref "R20") (pin "2") (pinfunction "2_2") (pintype "passive"))
    )
    (net (code "58") (name "/USB_BOOT") (class "Default")
      (node (ref "C41") (pin "2") (pinfunction "2_2") (pintype "passive"))
      (node (ref "JP1") (pin "2") (pinfunction "B_2") (pintype "passive"))
      (node (ref "R1") (pin "1") (pinfunction "1_1") (pintype "passive"))
      (node (ref "S2") (pin "3") (pinfunction "3_3") (pintype "passive"))
      (node (ref "S2") (pin "4") (pinfunction "4_4") (pintype "passive"))
    )
    (net (code "59") (name "/USB_N") (class "Default")
      (node (ref "IC2") (pin "46") (pinfunction "USB_DM_46") (pintype "passive"))
      (node (ref "R21") (pin "1") (pinfunction "1_1") (pintype "passive"))
    )
    (net (code "60") (name "/USB_P") (class "Default")
      (node (ref "IC2") (pin "47") (pinfunction "USB_DP_47") (pintype "passive"))
      (node (ref "R20") (pin "1") (pinfunction "1_1") (pintype "passive"))
    )
    (net (code "61") (name "GND") (class "Default")
      (node (ref "C1") (pin "1") (pinfunction "1_1") (pintype "passive"))
      (node (ref "C10") (pin "1") (pinfunction "1_1") (pintype "passive"))
      (node (ref "C11") (pin "1") (pinfunction "1_1") (pintype "passive"))
      (node (ref "C12") (pin "1") (pinfunction "1_1") (pintype "passive"))
      (node (ref "C14") (pin "1") (pinfunction "1_1") (pintype "passive"))
      (node (ref "C15") (pin "1") (pinfunction "1_1") (pintype "passive"))
      (node (ref "C16") (pin "1") (pinfunction "1_1") (pintype "passive"))
      (node (ref "C2") (pin "1") (pinfunction "1_1") (pintype "passive"))
      (node (ref "C3") (pin "1") (pinfunction "1_1") (pintype "passive"))
      (node (ref "C4") (pin "1") (pinfunction "1_1") (pintype "passive"))
      (node (ref "C40") (pin "1") (pinfunction "1_1") (pintype "passive"))
      (node (ref "C41") (pin "1") (pinfunction "1_1") (pintype "passive"))
      (node (ref "C5") (pin "1") (pinfunction "1_1") (pintype "passive"))
      (node (ref "C6") (pin "1") (pinfunction "1_1") (pintype "passive"))
      (node (ref "C7") (pin "1") (pinfunction "1_1") (pintype "passive"))
      (node (ref "C8") (pin "1") (pinfunction "1_1") (pintype "passive"))
      (node (ref "C9") (pin "1") (pinfunction "1_1") (pintype "passive"))
      (node (ref "IC1") (pin "4") (pinfunction "GND_4") (pintype "passive"))
      (node (ref "IC1") (pin "9") (pinfunction "EP_9") (pintype "passive"))
      (node (ref "IC2") (pin "19") (pinfunction "TESTEN_19") (pintype "passive"))
      (node (ref "IC2") (pin "57") (pinfunction "GND_57") (pintype "passive"))
      (node (ref "J1") (pin "10") (pinfunction "CD_10") (pintype "passive"))
      (node (ref "J1") (pin "6") (pinfunction "VSS_6") (pintype "passive"))
      (node (ref "J1") (pin "S") (pinfunction "SHLD_S") (pintype "passive"))
      (node (ref "JP1") (pin "1") (pinfunction "A_1") (pintype "passive"))
      (node (ref "P2") (pin "3") (pinfunction "3_3") (pintype "passive"))
      (node (ref "P2") (pin "5") (pinfunction "5_5") (pintype "passive"))
      (node (ref "P2") (pin "7") (pinfunction "7_7") (pintype "passive"))
      (node (ref "P2") (pin "9") (pinfunction "9_9") (pintype "passive"))
      (node (ref "R23") (pin "1") (pinfunction "1_1") (pintype "passive"))
      (node (ref "S1") (pin "3") (pinfunction "3_3") (pintype "passive"))
      (node (ref "S1") (pin "4") (pinfunction "4_4") (pintype "passive"))
      (node (ref "S2") (pin "1") (pinfunction "1_1") (pintype "passive"))
      (node (ref "S2") (pin "2") (pinfunction "2_2") (pintype "passive"))
      (node (ref "Y1") (pin "2") (pinfunction "GND_2") (pintype "passive"))
      (node (ref "Y1") (pin "4") (pinfunction "GND_4") (pintype "passive"))
    )
    (net (code "62") (name "Net-(C9-Pad2)") (class "Default")
      (node (ref "C9") (pin "2") (pinfunction "2_2") (pintype "passive"))
      (node (ref "R17") (pin "1") (pinfunction "1_1") (pintype "passive"))
      (node (ref "Y1") (pin "3") (pinfunction "3_3") (pintype "passive"))
    )
    (net (code "63") (name "Net-(D1-Pad2)") (class "Default")
      (node (ref "D1") (pin "2") (pinfunction "2_2") (pintype "passive"))
      (node (ref "R23") (pin "2") (pinfunction "2_2") (pintype "passive"))
    )
    (net (code "64") (name "Net-(IC2A-XIN)") (class "Default")
      (node (ref "C6") (pin "2") (pinfunction "2_2") (pintype "passive"))
      (node (ref "IC2") (pin "20") (pinfunction "XIN_20") (pintype "passive"))
      (node (ref "Y1") (pin "1") (pinfunction "1_1") (pintype "passive"))
    )
    (net (code "65") (name "Net-(IC2A-XOUT)") (class "Default")
      (node (ref "IC2") (pin "21") (pinfunction "XOUT_21") (pintype "passive"))
      (node (ref "R17") (pin "2") (pinfunction "2_2") (pintype "passive"))
    )
    (net (code "66") (name "Net-(IC2B-GPIO14)") (class "Default")
      (node (ref "IC2") (pin "17") (pinfunction "GPIO14_17") (pintype "passive"))
      (node (ref "R22") (pin "2") (pinfunction "2_2") (pintype "passive"))
    )
    (net (code "67") (name "unconnected-(J1-DAT1-Pad8)") (class "Default")
      (node (ref "J1") (pin "8") (pinfunction "DAT1_8") (pintype "passive"))
    )
    (net (code "68") (name "unconnected-(J1-DAT2-Pad1)") (class "Default")
      (node (ref "J1") (pin "1") (pinfunction "DAT2_1") (pintype "passive"))
    )
    (net (code "69") (name "unconnected-(P2-Pad6)") (class "Default")
      (node (ref "P2") (pin "6") (pinfunction "6_6") (pintype "passive"))
    )
    (net (code "70") (name "unconnected-(P2-Pad8)") (class "Default")
      (node (ref "P2") (pin "8") (pinfunction "8_8") (pintype "passive"))
    )
  )
)
